# untitled.net
KiCad netlist of a schematic drawn in EAGLE
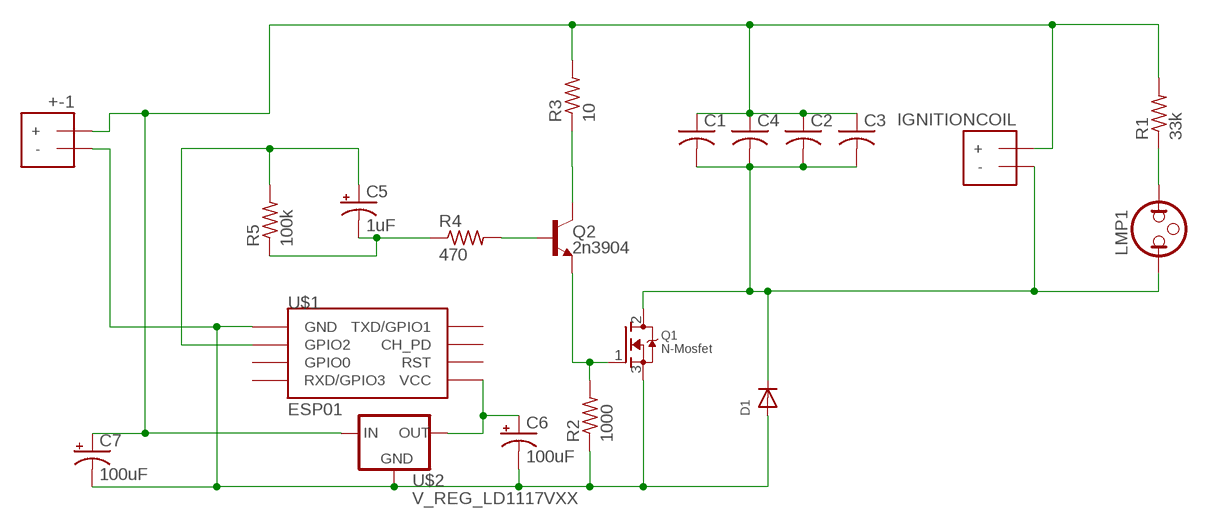
[diagram p0: schematic, sheet 1]

(export (version "E")
  (design (tool "Eeschema 10.0.6"))
  (components
    (comp (ref "+-1")
      (value "1X2_-++-")
      (footprint "eagle-import:1X2_+-")
      (libsource (lib "eagle-import") (part "1X2_-++-"))
    )
    (comp (ref "C1")
      (value "C-US225-062X268")
      (footprint "eagle-import:C225-062X268")
      (libsource (lib "eagle-import") (part "C-US225-062X268"))
    )
    (comp (ref "C2")
      (value "C-US225-062X268")
      (footprint "eagle-import:C225-062X268")
      (libsource (lib "eagle-import") (part "C-US225-062X268"))
    )
    (comp (ref "C3")
      (value "C-US225-062X268")
      (footprint "eagle-import:C225-062X268")
      (libsource (lib "eagle-import") (part "C-US225-062X268"))
    )
    (comp (ref "C4")
      (value "C-US225-062X268")
      (footprint "eagle-import:C225-062X268")
      (libsource (lib "eagle-import") (part "C-US225-062X268"))
    )
    (comp (ref "C5")
      (value "1uF")
      (footprint "eagle-import:E2-5")
      (libsource (lib "eagle-import") (part "CPOL-USE2-5"))
    )
    (comp (ref "C6")
      (value "100uF")
      (footprint "eagle-import:E2,5-6")
      (libsource (lib "eagle-import") (part "CPOL-USE2.5-6"))
    )
    (comp (ref "C7")
      (value "100uF")
      (footprint "eagle-import:E2,5-6")
      (libsource (lib "eagle-import") (part "CPOL-USE2.5-6"))
    )
    (comp (ref "D1")
      (value "DIODEDO-1N4148")
      (footprint "eagle-import:DO-1N4148")
      (libsource (lib "eagle-import") (part "DIODEDO-1N4148"))
    )
    (comp (ref "IGNITIONCOIL")
      (value "1X2_-++-")
      (footprint "eagle-import:1X2_+-")
      (libsource (lib "eagle-import") (part "1X2_-++-"))
    )
    (comp (ref "LMP1")
      (value "NEON")
      (footprint "eagle-import:LDH-3R")
      (libsource (lib "eagle-import") (part "NEON"))
    )
    (comp (ref "Q1")
      (value "N-Mosfet")
      (footprint "eagle-import:TO220V")
      (libsource (lib "eagle-import") (part "MOSFET-NGDS_TO220V"))
    )
    (comp (ref "Q2")
      (value "2n3904")
      (footprint "eagle-import:TO-92INSERT")
      (libsource (lib "eagle-import") (part "TRANS_NPN"))
    )
    (comp (ref "R1")
      (value "33k")
      (footprint "eagle-import:0204_7")
      (libsource (lib "eagle-import") (part "R-US_0204/7"))
    )
    (comp (ref "R2")
      (value "1000")
      (footprint "eagle-import:0204_7")
      (libsource (lib "eagle-import") (part "R-US_0204/7"))
    )
    (comp (ref "R3")
      (value "10")
      (footprint "eagle-import:0204_7")
      (libsource (lib "eagle-import") (part "R-US_0204/7"))
    )
    (comp (ref "R4")
      (value "470")
      (footprint "eagle-import:0204_7")
      (libsource (lib "eagle-import") (part "R-US_0204/7"))
    )
    (comp (ref "R5")
      (value "100k")
      (footprint "eagle-import:0204_7")
      (libsource (lib "eagle-import") (part "R-US_0204/7"))
    )
    (comp (ref "U$1")
      (value "ESP01")
      (footprint "eagle-import:ESP01")
      (libsource (lib "eagle-import") (part "ESP01"))
    )
    (comp (ref "U$2")
      (value "V_REG_LD1117VXX")
      (footprint "eagle-import:78XXL")
      (libsource (lib "eagle-import") (part "V_REG_LD1117VXX"))
    )
  )
  (nets
    (net (code "1") (name "Net-(C5-Pad+)") (class "Default")
      (node (ref "C5") (pin "+") (pinfunction "+_+") (pintype "passive"))
      (node (ref "R5") (pin "2") (pinfunction "2_2") (pintype "passive"))
      (node (ref "U$1") (pin "GPIO2") (pinfunction "GPIO2_GPIO2") (pintype "bidirectional"))
    )
    (net (code "2") (name "Net-(C5-Pad-)") (class "Default")
      (node (ref "C5") (pin "-") (pinfunction "-_-") (pintype "passive"))
      (node (ref "R4") (pin "1") (pinfunction "1_1") (pintype "passive"))
      (node (ref "R5") (pin "1") (pinfunction "1_1") (pintype "passive"))
    )
    (net (code "3") (name "Net-(LMP1-Pad2)") (class "Default")
      (node (ref "LMP1") (pin "2") (pinfunction "2_2") (pintype "passive"))
      (node (ref "R1") (pin "1") (pinfunction "1_1") (pintype "passive"))
    )
    (net (code "4") (name "Net-(Q1-D)") (class "Default")
      (node (ref "C1") (pin "2") (pinfunction "2_2") (pintype "passive"))
      (node (ref "C2") (pin "2") (pinfunction "2_2") (pintype "passive"))
      (node (ref "C3") (pin "2") (pinfunction "2_2") (pintype "passive"))
      (node (ref "C4") (pin "2") (pinfunction "2_2") (pintype "passive"))
      (node (ref "D1") (pin "C") (pinfunction "C_C") (pintype "passive"))
      (node (ref "IGNITIONCOIL") (pin "-") (pinfunction "-_-") (pintype "passive"))
      (node (ref "LMP1") (pin "1") (pinfunction "1_1") (pintype "passive"))
      (node (ref "Q1") (pin "2") (pinfunction "D_2") (pintype "bidirectional"))
    )
    (net (code "5") (name "Net-(Q1-G)") (class "Default")
      (node (ref "Q1") (pin "1") (pinfunction "G_1") (pintype "bidirectional"))
      (node (ref "Q2") (pin "3") (pinfunction "E_3") (pintype "passive"))
      (node (ref "R2") (pin "2") (pinfunction "2_2") (pintype "passive"))
    )
    (net (code "6") (name "Net-(Q1-S)") (class "Default")
      (node (ref "+-1") (pin "-") (pinfunction "-_-") (pintype "passive"))
      (node (ref "C6") (pin "-") (pinfunction "-_-") (pintype "passive"))
      (node (ref "C7") (pin "-") (pinfunction "-_-") (pintype "passive"))
      (node (ref "D1") (pin "A") (pinfunction "A_A") (pintype "passive"))
      (node (ref "Q1") (pin "3") (pinfunction "S_3") (pintype "bidirectional"))
      (node (ref "R2") (pin "1") (pinfunction "1_1") (pintype "passive"))
      (node (ref "U$1") (pin "GND") (pinfunction "GND_GND") (pintype "bidirectional"))
      (node (ref "U$2") (pin "IN") (pinfunction "GND_IN") (pintype "input"))
    )
    (net (code "7") (name "Net-(Q2-B)") (class "Default")
      (node (ref "Q2") (pin "2") (pinfunction "B_2") (pintype "passive"))
      (node (ref "R4") (pin "2") (pinfunction "2_2") (pintype "passive"))
    )
    (net (code "8") (name "Net-(Q2-C)") (class "Default")
      (node (ref "Q2") (pin "1") (pinfunction "C_1") (pintype "passive"))
      (node (ref "R3") (pin "1") (pinfunction "1_1") (pintype "passive"))
    )
    (net (code "9") (name "Net-(U$2-IN)") (class "Default")
      (node (ref "+-1") (pin "+") (pinfunction "+_+") (pintype "passive"))
      (node (ref "C1") (pin "1") (pinfunction "1_1") (pintype "passive"))
      (node (ref "C2") (pin "1") (pinfunction "1_1") (pintype "passive"))
      (node (ref "C3") (pin "1") (pinfunction "1_1") (pintype "passive"))
      (node (ref "C4") (pin "1") (pinfunction "1_1") (pintype "passive"))
      (node (ref "C7") (pin "+") (pinfunction "+_+") (pintype "passive"))
      (node (ref "IGNITIONCOIL") (pin "+") (pinfunction "+_+") (pintype "passive"))
      (node (ref "R1") (pin "2") (pinfunction "2_2") (pintype "passive"))
      (node (ref "R3") (pin "2") (pinfunction "2_2") (pintype "passive"))
      (node (ref "U$2") (pin "OUT") (pinfunction "IN_OUT") (pintype "input"))
    )
    (net (code "10") (name "Net-(U$2-OUT)") (class "Default")
      (node (ref "C6") (pin "+") (pinfunction "+_+") (pintype "passive"))
      (node (ref "U$1") (pin "VCC") (pinfunction "VCC_VCC") (pintype "bidirectional"))
      (node (ref "U$2") (pin "GND") (pinfunction "OUT_GND") (pintype "passive"))
    )
    (net (code "11") (name "unconnected-(U$1-PadCH_PD)") (class "Default")
      (node (ref "U$1") (pin "CH_PD") (pinfunction "CH_PD_CH_PD") (pintype "bidirectional"))
    )
    (net (code "12") (name "unconnected-(U$1-PadGPIO0)") (class "Default")
      (node (ref "U$1") (pin "GPIO0") (pinfunction "GPIO0_GPIO0") (pintype "bidirectional"))
    )
    (net (code "13") (name "unconnected-(U$1-PadRST)") (class "Default")
      (node (ref "U$1") (pin "RST") (pinfunction "RST_RST") (pintype "bidirectional"))
    )
    (net (code "14") (name "unconnected-(U$1-RXD{slash}GPIO3-PadRX)") (class "Default")
      (node (ref "U$1") (pin "RX") (pinfunction "RXD/GPIO3_RX") (pintype "bidirectional"))
    )
    (net (code "15") (name "unconnected-(U$1-TXD{slash}GPIO1-PadTX)") (class "Default")
      (node (ref "U$1") (pin "TX") (pinfunction "TXD/GPIO1_TX") (pintype "bidirectional"))
    )
  )
)
